# AIRZAI_LED_SENSE_FLEX_REVA.net
KiCad netlist of a schematic drawn in Altium Designer
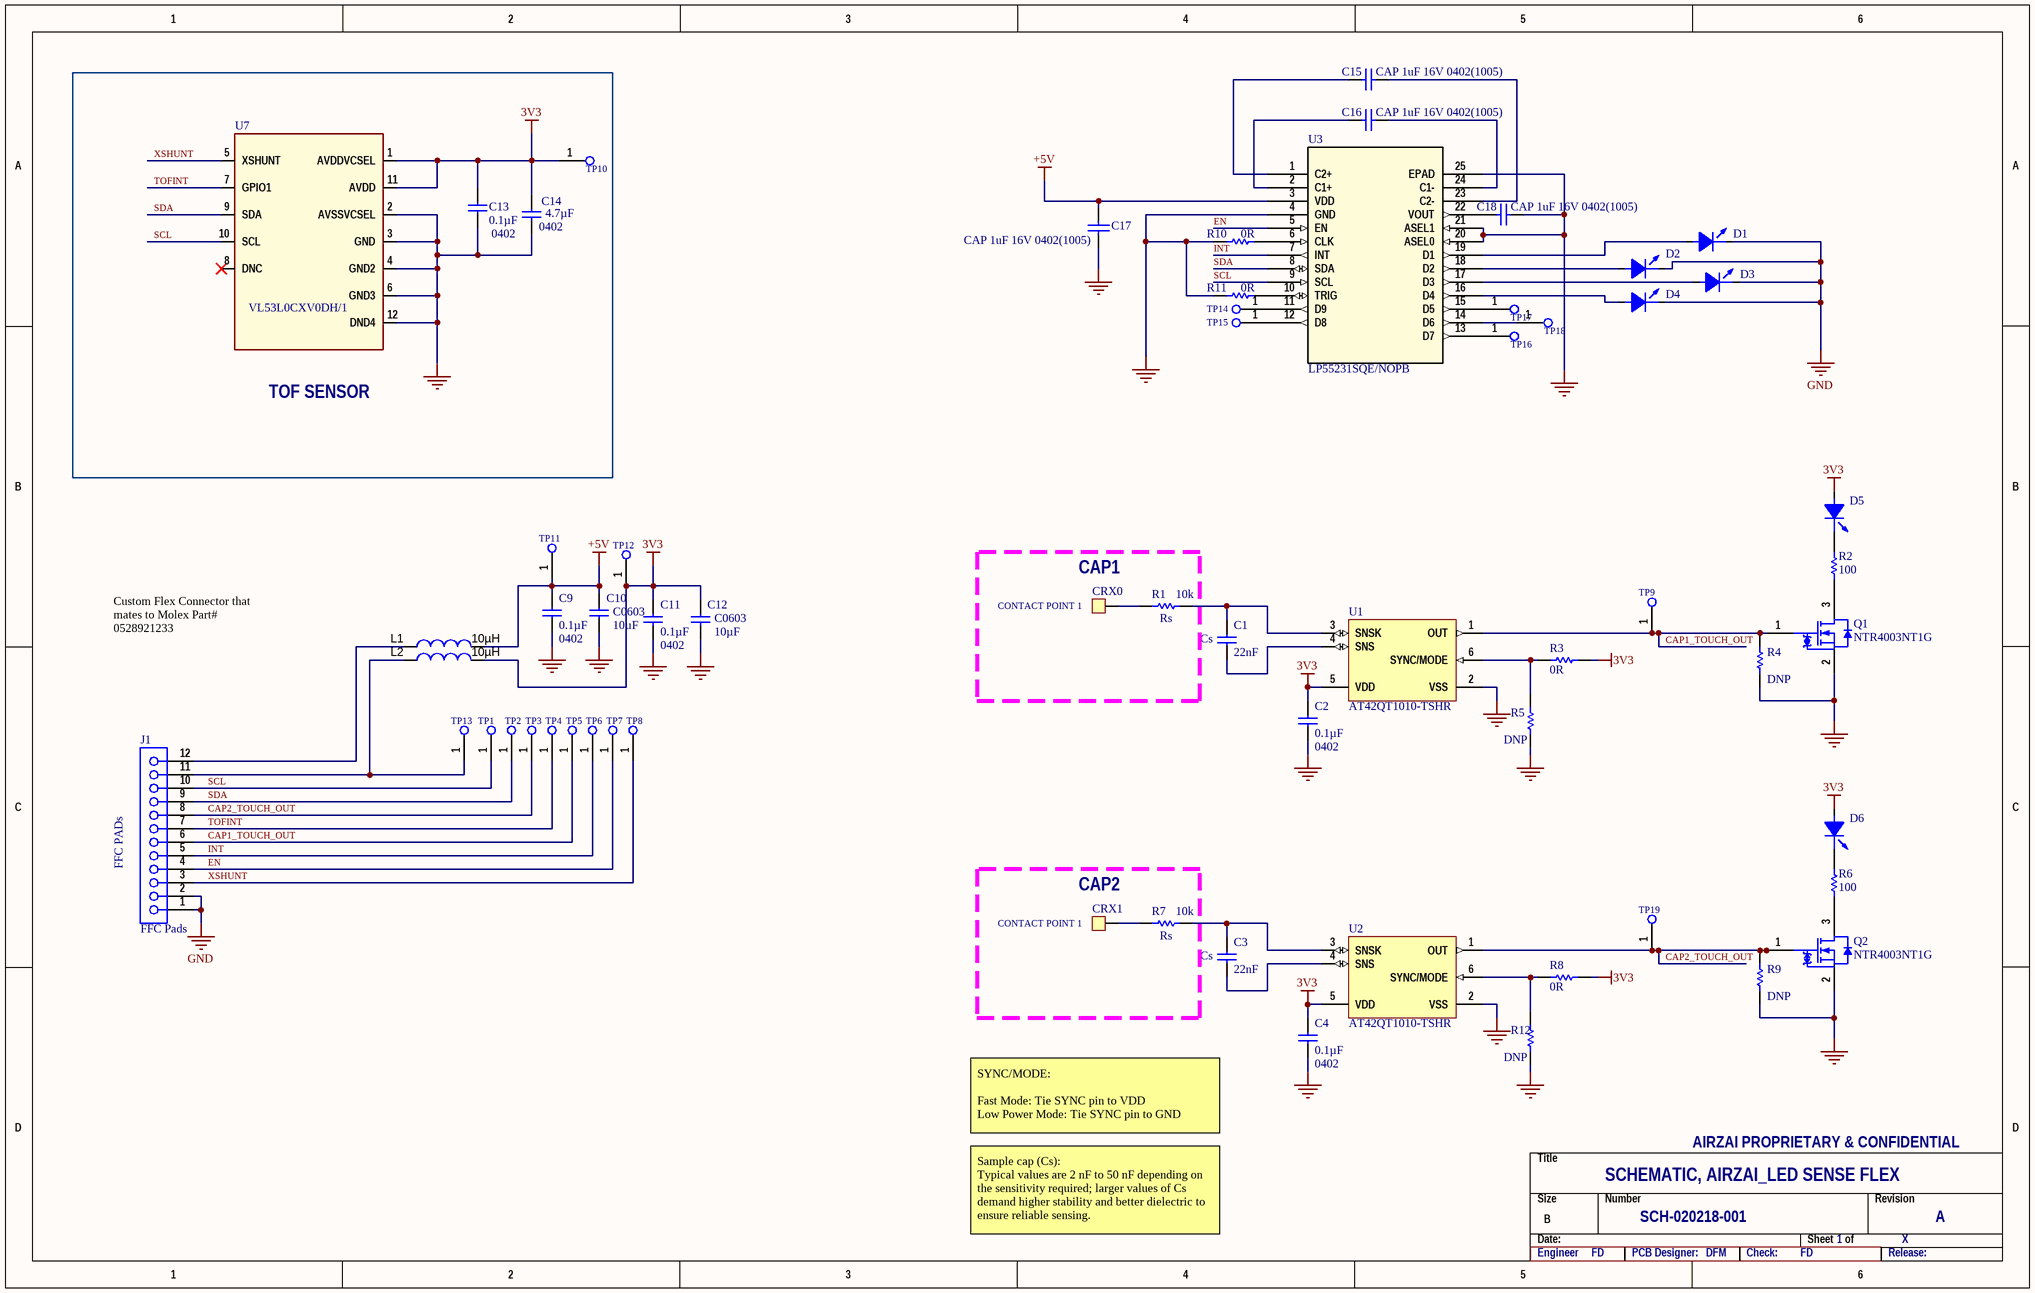
[diagram p0: AIRZAI_LED_SENSE_FLEX_REVA.SchDoc]

(export (version "E")
  (design (tool "Eeschema 10.0.6"))
  (components
    (comp (ref "C1")
      (value "22nF")
      (footprint "0402CAP")
      (description "Capacitor, X7R, ±10%")
      (fields
        (field (name "MANUFACTURER") "TDK")
        (field (name "MANUFACTURER PART NUMBER") "CGA2B2X7R1E223K050BA")
      )
      (libsource (lib "Nordic Passive DB") (part "CAP"))
    )
    (comp (ref "C2")
      (value "0.1µF")
      (footprint "0402")
      (description "Capacitor, X7R, ±10%")
      (fields (field (name "MANUFACTURER") "TDK") (field (name "MANUFACTURER PART NUMBER") "C1005X7R1C104K"))
      (libsource (lib "Nordic Passive DB") (part "CAP"))
    )
    (comp (ref "C3")
      (value "22nF")
      (footprint "0402CAP")
      (description "Capacitor, X7R, ±10%")
      (fields
        (field (name "MANUFACTURER") "TDK")
        (field (name "MANUFACTURER PART NUMBER") "CGA2B2X7R1E223K050BA")
      )
      (libsource (lib "Nordic Passive DB") (part "CAP"))
    )
    (comp (ref "C4")
      (value "0.1µF")
      (footprint "0402")
      (description "Capacitor, X7R, ±10%")
      (fields (field (name "MANUFACTURER") "TDK") (field (name "MANUFACTURER PART NUMBER") "C1005X7R1C104K"))
      (libsource (lib "Nordic Passive DB") (part "CAP"))
    )
    (comp (ref "C9")
      (value "0.1µF")
      (footprint "0402")
      (description "Capacitor, X7R, ±10%")
      (fields (field (name "MANUFACTURER") "TDK") (field (name "MANUFACTURER PART NUMBER") "C1005X7R1C104K"))
      (libsource (lib "Nordic Passive DB") (part "CAP"))
    )
    (comp (ref "C10")
      (value "10µF")
      (footprint "C0603")
      (description "Capacitor, X7R, ±10%")
      (fields
        (field (name "MANUFACTURER") "MURATA")
        (field (name "MANUFACTURER PART NUMBER") "GRM188R60J106ME47D")
      )
      (libsource (lib "Nordic Passive DB") (part "CAP"))
    )
    (comp (ref "C11")
      (value "0.1µF")
      (footprint "0402")
      (description "Capacitor, X7R, ±10%")
      (fields (field (name "MANUFACTURER") "TDK") (field (name "MANUFACTURER PART NUMBER") "C1005X7R1C104K"))
      (libsource (lib "Nordic Passive DB") (part "CAP"))
    )
    (comp (ref "C12")
      (value "10µF")
      (footprint "C0603")
      (description "Capacitor, X7R, ±10%")
      (fields
        (field (name "MANUFACTURER") "MURATA")
        (field (name "MANUFACTURER PART NUMBER") "GRM188R60J106ME47D")
      )
      (libsource (lib "Nordic Passive DB") (part "CAP"))
    )
    (comp (ref "C13")
      (value "0.1µF")
      (footprint "0402")
      (description "Capacitor, X7R, ±10%")
      (fields (field (name "MANUFACTURER") "TDK") (field (name "MANUFACTURER PART NUMBER") "C1005X7R1C104K"))
      (libsource (lib "Nordic Passive DB") (part "CAP"))
    )
    (comp (ref "C14")
      (value "4.7µF")
      (footprint "0402")
      (description "Capacitor, X7R, ±10%")
      (fields (field (name "MANUFACTURER") "TDK") (field (name "MANUFACTURER PART NUMBER") "C1005X5R0J475M"))
      (libsource (lib "Nordic Passive DB") (part "CAP"))
    )
    (comp (ref "C15")
      (value "CAP 1uF 16V 0402(1005)")
      (footprint "CAPC0402(1005)60_M")
      (description "CAP 1uF 16V ±10% 0402 (1005 Metric) Thickness 0.6mm SMD")
      (fields (field (name "TOLERANCE") "Â±10%") (field (name "MANUFACTURER") "Taiyo Yuden"))
      (libsource (lib "AIRZAI_LED_SENSE_FLEX_REVA") (part "CAP"))
    )
    (comp (ref "C16")
      (value "CAP 1uF 16V 0402(1005)")
      (footprint "CAPC0402(1005)60_M")
      (description "CAP 1uF 16V ±10% 0402 (1005 Metric) Thickness 0.6mm SMD")
      (fields (field (name "TOLERANCE") "Â±10%") (field (name "MANUFACTURER") "Taiyo Yuden"))
      (libsource (lib "AIRZAI_LED_SENSE_FLEX_REVA") (part "CAP"))
    )
    (comp (ref "C17")
      (value "CAP 1uF 16V 0402(1005)")
      (footprint "CAPC0402(1005)60_M")
      (description "CAP 1uF 16V ±10% 0402 (1005 Metric) Thickness 0.6mm SMD")
      (fields (field (name "TOLERANCE") "Â±10%") (field (name "MANUFACTURER") "Taiyo Yuden"))
      (libsource (lib "AIRZAI_LED_SENSE_FLEX_REVA") (part "CAP"))
    )
    (comp (ref "C18")
      (value "CAP 1uF 16V 0402(1005)")
      (footprint "CAPC0402(1005)60_M")
      (description "CAP 1uF 16V ±10% 0402 (1005 Metric) Thickness 0.6mm SMD")
      (fields (field (name "TOLERANCE") "Â±10%") (field (name "MANUFACTURER") "Taiyo Yuden"))
      (libsource (lib "AIRZAI_LED_SENSE_FLEX_REVA") (part "CAP"))
    )
    (comp (ref "CRX0")
      (value "CONTACT POINT 1")
      (footprint "CONTACT_POINT_1CM _SQ")
      (libsource (lib "AIRZAI_LED_SENSE_FLEX_REVA") (part "WIRE_POINT"))
    )
    (comp (ref "CRX1")
      (value "CONTACT POINT 1")
      (footprint "CONTACT_POINT_1CM _SQ")
      (libsource (lib "AIRZAI_LED_SENSE_FLEX_REVA") (part "WIRE_POINT"))
    )
    (comp (ref "D1")
      (value "WHITE")
      (footprint "LED1206_LTW-C230DS")
      (fields (field (name "MANUFACTURER PART NUMBER") "LTW-C230DS") (field (name "MANUFACTURER") "LITEON"))
      (libsource (lib "AIRZAI_LED_SENSE_FLEX_REVA") (part "LED_LTW-C230DS"))
    )
    (comp (ref "D2")
      (value "WHITE")
      (footprint "LED1206_LTW-C230DS")
      (fields (field (name "MANUFACTURER PART NUMBER") "LTW-C230DS") (field (name "MANUFACTURER") "LITEON"))
      (libsource (lib "AIRZAI_LED_SENSE_FLEX_REVA") (part "LED_LTW-C230DS"))
    )
    (comp (ref "D3")
      (value "WHITE")
      (footprint "LED1206_LTW-C230DS")
      (fields (field (name "MANUFACTURER PART NUMBER") "LTW-C230DS") (field (name "MANUFACTURER") "LITEON"))
      (libsource (lib "AIRZAI_LED_SENSE_FLEX_REVA") (part "LED_LTW-C230DS"))
    )
    (comp (ref "D4")
      (value "WHITE")
      (footprint "LED1206_LTW-C230DS")
      (fields (field (name "MANUFACTURER PART NUMBER") "LTW-C230DS") (field (name "MANUFACTURER") "LITEON"))
      (libsource (lib "AIRZAI_LED_SENSE_FLEX_REVA") (part "LED_LTW-C230DS"))
    )
    (comp (ref "D5")
      (value "WHITE")
      (footprint "LED1206_LTW-C230DS")
      (fields (field (name "MANUFACTURER PART NUMBER") "LTW-C230DS") (field (name "MANUFACTURER") "LITEON"))
      (libsource (lib "AIRZAI_LED_SENSE_FLEX_REVA") (part "LED_LTW-C230DS"))
    )
    (comp (ref "D6")
      (value "WHITE")
      (footprint "LED1206_LTW-C230DS")
      (fields (field (name "MANUFACTURER PART NUMBER") "LTW-C230DS") (field (name "MANUFACTURER") "LITEON"))
      (libsource (lib "AIRZAI_LED_SENSE_FLEX_REVA") (part "LED_LTW-C230DS"))
    )
    (comp (ref "J1")
      (value "FFC Pads")
      (footprint "FFC_Pads")
      (description "0.5 mm Pitch FFC Pads")
      (libsource (lib "AIRZAI_LED_SENSE_FLEX_REVA") (part "FFC_PADS"))
    )
    (comp (ref "L1")
      (value "CB2012T100KR")
      (footprint "0805")
      (description "Inductor, 10 µH, 0.5A, 0.65 ohm, SMD")
      (fields
        (field (name "MANUFACTURER") "Taiyo Yuden")
        (field (name "TOLERANCE") "10%")
        (field (name "VALUEDISPLAYED") "10µH")
      )
      (libsource (lib "AIRZAI_LED_SENSE_FLEX_REVA") (part "CB2012T100KR"))
    )
    (comp (ref "L2")
      (value "CB2012T100KR")
      (footprint "0805")
      (description "Inductor, 10 µH, 0.5A, 0.65 ohm, SMD")
      (fields
        (field (name "MANUFACTURER") "Taiyo Yuden")
        (field (name "TOLERANCE") "10%")
        (field (name "VALUEDISPLAYED") "10µH")
      )
      (libsource (lib "AIRZAI_LED_SENSE_FLEX_REVA") (part "CB2012T100KR"))
    )
    (comp (ref "Q1")
      (value "NTR4003NT1G")
      (footprint "SOT-23-3-NTR4003NT1G")
      (description "N-Channel 30V 500mA (Ta) 690mW (Ta) Surface Mount SOT-23-3 (TO-236)")
      (fields (field (name "MANUFACTURER") "ON Semiconductor"))
      (libsource (lib "AIRZAI_LED_SENSE_FLEX_REVA") (part "NTR4003NT1G"))
    )
    (comp (ref "Q2")
      (value "NTR4003NT1G")
      (footprint "SOT-23-3-NTR4003NT1G")
      (description "N-Channel 30V 500mA (Ta) 690mW (Ta) Surface Mount SOT-23-3 (TO-236)")
      (fields (field (name "MANUFACTURER") "ON Semiconductor"))
      (libsource (lib "AIRZAI_LED_SENSE_FLEX_REVA") (part "NTR4003NT1G"))
    )
    (comp (ref "R1")
      (value "10k")
      (footprint "0402")
      (description "10k 0.063W 1% 0402 (1005 Metric)  SMD")
      (fields (field (name "TOLERANCE") "None") (field (name "POWER") "0.063W"))
      (libsource (lib "AIRZAI_LED_SENSE_FLEX_REVA") (part "RES"))
    )
    (comp (ref "R2")
      (value "100")
      (footprint "0402")
      (description "100 0.063W 1% 0402 (1005 Metric)  SMD")
      (fields (field (name "TOLERANCE") "None") (field (name "MANUFACTURER") "Yageo"))
      (libsource (lib "AIRZAI_LED_SENSE_FLEX_REVA") (part "RES"))
    )
    (comp (ref "R3")
      (value "0R")
      (footprint "0402")
      (description "Jumper 0402 (1005 Metric)")
      (fields (field (name "TOLERANCE") "None") (field (name "MANUFACTURER") "Panasonic"))
      (libsource (lib "AIRZAI_LED_SENSE_FLEX_REVA") (part "RES"))
    )
    (comp (ref "R4")
      (value "DNP")
      (footprint "0402")
      (fields
        (field (name "TOLERANCE") "None")
        (field (name "POWER") "0.0625 W")
        (field (name "Comment") "DNP 0402(1005)")
      )
      (libsource (lib "AIRZAI_LED_SENSE_FLEX_REVA") (part "RES"))
    )
    (comp (ref "R5")
      (value "DNP")
      (footprint "0402")
      (fields
        (field (name "TOLERANCE") "None")
        (field (name "POWER") "0.0625 W")
        (field (name "Comment") "DNP 0402(1005)")
      )
      (libsource (lib "AIRZAI_LED_SENSE_FLEX_REVA") (part "RES"))
    )
    (comp (ref "R6")
      (value "100")
      (footprint "0402")
      (description "100 0.063W 1% 0402 (1005 Metric)  SMD")
      (fields (field (name "TOLERANCE") "None") (field (name "MANUFACTURER") "Yageo"))
      (libsource (lib "AIRZAI_LED_SENSE_FLEX_REVA") (part "RES"))
    )
    (comp (ref "R7")
      (value "10k")
      (footprint "0402")
      (description "10k 0.063W 1% 0402 (1005 Metric)  SMD")
      (fields (field (name "TOLERANCE") "None") (field (name "POWER") "0.063W"))
      (libsource (lib "AIRZAI_LED_SENSE_FLEX_REVA") (part "RES"))
    )
    (comp (ref "R8")
      (value "0R")
      (footprint "0402")
      (description "Jumper 0402 (1005 Metric)")
      (fields (field (name "TOLERANCE") "None") (field (name "MANUFACTURER") "Panasonic"))
      (libsource (lib "AIRZAI_LED_SENSE_FLEX_REVA") (part "RES"))
    )
    (comp (ref "R9")
      (value "DNP")
      (footprint "0402")
      (fields
        (field (name "TOLERANCE") "None")
        (field (name "POWER") "0.0625 W")
        (field (name "Comment") "DNP 0402(1005)")
      )
      (libsource (lib "AIRZAI_LED_SENSE_FLEX_REVA") (part "RES"))
    )
    (comp (ref "R10")
      (value "0R")
      (footprint "0402")
      (description "Jumper 0402 (1005 Metric)")
      (fields (field (name "TOLERANCE") "None") (field (name "MANUFACTURER") "Panasonic"))
      (libsource (lib "AIRZAI_LED_SENSE_FLEX_REVA") (part "RES"))
    )
    (comp (ref "R11")
      (value "0R")
      (footprint "0402")
      (description "Jumper 0402 (1005 Metric)")
      (fields (field (name "TOLERANCE") "None") (field (name "MANUFACTURER") "Panasonic"))
      (libsource (lib "AIRZAI_LED_SENSE_FLEX_REVA") (part "RES"))
    )
    (comp (ref "R12")
      (value "DNP")
      (footprint "0402")
      (fields
        (field (name "TOLERANCE") "None")
        (field (name "POWER") "0.0625 W")
        (field (name "Comment") "DNP 0402(1005)")
      )
      (libsource (lib "AIRZAI_LED_SENSE_FLEX_REVA") (part "RES"))
    )
    (comp (ref "TP1")
      (value "Test Point")
      (footprint "TP_0.9MM")
      (libsource (lib "AIRZAI_LED_SENSE_FLEX_REVA") (part "Test Point"))
    )
    (comp (ref "TP2")
      (value "Test Point")
      (footprint "TP_0.9MM")
      (libsource (lib "AIRZAI_LED_SENSE_FLEX_REVA") (part "Test Point"))
    )
    (comp (ref "TP3")
      (value "Test Point")
      (footprint "TP_0.9MM")
      (libsource (lib "AIRZAI_LED_SENSE_FLEX_REVA") (part "Test Point"))
    )
    (comp (ref "TP4")
      (value "Test Point")
      (footprint "TP_0.9MM")
      (libsource (lib "AIRZAI_LED_SENSE_FLEX_REVA") (part "Test Point"))
    )
    (comp (ref "TP5")
      (value "Test Point")
      (footprint "TP_0.9MM")
      (libsource (lib "AIRZAI_LED_SENSE_FLEX_REVA") (part "Test Point"))
    )
    (comp (ref "TP6")
      (value "Test Point")
      (footprint "TP_0.9MM")
      (libsource (lib "AIRZAI_LED_SENSE_FLEX_REVA") (part "Test Point"))
    )
    (comp (ref "TP7")
      (value "Test Point")
      (footprint "TP_0.9MM")
      (libsource (lib "AIRZAI_LED_SENSE_FLEX_REVA") (part "Test Point"))
    )
    (comp (ref "TP8")
      (value "Test Point")
      (footprint "TP_0.9MM")
      (libsource (lib "AIRZAI_LED_SENSE_FLEX_REVA") (part "Test Point"))
    )
    (comp (ref "TP9")
      (value "Test Point")
      (footprint "TP_0.9MM")
      (libsource (lib "AIRZAI_LED_SENSE_FLEX_REVA") (part "Test Point"))
    )
    (comp (ref "TP10")
      (value "Test Point")
      (footprint "TP_0.9MM")
      (libsource (lib "AIRZAI_LED_SENSE_FLEX_REVA") (part "Test Point"))
    )
    (comp (ref "TP11")
      (value "Test Point")
      (footprint "TP_0.9MM")
      (libsource (lib "AIRZAI_LED_SENSE_FLEX_REVA") (part "Test Point"))
    )
    (comp (ref "TP12")
      (value "Test Point")
      (footprint "TP_0.9MM")
      (libsource (lib "AIRZAI_LED_SENSE_FLEX_REVA") (part "Test Point"))
    )
    (comp (ref "TP13")
      (value "Test Point")
      (footprint "TP_0.9MM")
      (libsource (lib "AIRZAI_LED_SENSE_FLEX_REVA") (part "Test Point"))
    )
    (comp (ref "TP14")
      (value "Test Point")
      (footprint "TP_0.9MM")
      (libsource (lib "AIRZAI_LED_SENSE_FLEX_REVA") (part "Test Point"))
    )
    (comp (ref "TP15")
      (value "Test Point")
      (footprint "TP_0.9MM")
      (libsource (lib "AIRZAI_LED_SENSE_FLEX_REVA") (part "Test Point"))
    )
    (comp (ref "TP16")
      (value "Test Point")
      (footprint "TP_0.9MM")
      (libsource (lib "AIRZAI_LED_SENSE_FLEX_REVA") (part "Test Point"))
    )
    (comp (ref "TP17")
      (value "Test Point")
      (footprint "TP_0.9MM")
      (libsource (lib "AIRZAI_LED_SENSE_FLEX_REVA") (part "Test Point"))
    )
    (comp (ref "TP18")
      (value "Test Point")
      (footprint "TP_0.9MM")
      (libsource (lib "AIRZAI_LED_SENSE_FLEX_REVA") (part "Test Point"))
    )
    (comp (ref "TP19")
      (value "Test Point")
      (footprint "TP_0.9MM")
      (libsource (lib "AIRZAI_LED_SENSE_FLEX_REVA") (part "Test Point"))
    )
    (comp (ref "U1")
      (value "AT42QT1010-TSHR")
      (footprint "SOT-23-6-AT42QT1010-TSHR")
      (description "One-channel Touch Sensor IC with Reset Timer, -40° to +85° C, 6-pin SOT23")
      (libsource (lib "AIRZAI_LED_SENSE_FLEX_REVA") (part "AT42QT1010-TSHR"))
    )
    (comp (ref "U2")
      (value "AT42QT1010-TSHR")
      (footprint "SOT-23-6-AT42QT1010-TSHR")
      (description "One-channel Touch Sensor IC with Reset Timer, -40° to +85° C, 6-pin SOT23")
      (libsource (lib "AIRZAI_LED_SENSE_FLEX_REVA") (part "AT42QT1010-TSHR"))
    )
    (comp (ref "U3")
      (value "LP55231SQE/NOPB")
      (footprint "WQFN-24-LP55231SQE/NOPB")
      (description "Imported")
      (fields (field (name "MANUFACTURER") "TI") (field (name "TOLERANCE") "None"))
      (libsource (lib "AltiumDesigner") (part "LP55231SQE/NOPB"))
    )
    (comp (ref "U7")
      (value "VL53L0CXV0DH/1")
      (footprint "VL53L0X")
      (fields (field (name "MANUFACTURER") "ST") (field (name "TOLERANCE") "None"))
      (libsource (lib "DFM_JBKEGSVS_Library") (part "VL53L0X"))
    )
  )
  (nets
    (net (code "1") (name "+5V") (class "Default")
      (node (ref "C10") (pin "1") (pinfunction "1_1") (pintype "passive"))
      (node (ref "C17") (pin "2") (pinfunction "2_2") (pintype "passive"))
      (node (ref "C9") (pin "1") (pinfunction "1_1") (pintype "passive"))
      (node (ref "L1") (pin "2") (pinfunction "2_2") (pintype "passive"))
      (node (ref "TP11") (pin "1") (pinfunction "1_1") (pintype "passive"))
      (node (ref "U3") (pin "3") (pinfunction "VDD_3") (pintype "power_in"))
    )
    (net (code "2") (name "/CAP1_TOUCH_OUT") (class "Default")
      (node (ref "J1") (pin "6") (pinfunction "6_6") (pintype "passive"))
      (node (ref "Q1") (pin "1") (pinfunction "G_1") (pintype "passive"))
      (node (ref "R4") (pin "1") (pinfunction "1_1") (pintype "passive"))
      (node (ref "TP5") (pin "1") (pinfunction "1_1") (pintype "passive"))
      (node (ref "TP9") (pin "1") (pinfunction "1_1") (pintype "passive"))
      (node (ref "U1") (pin "1") (pinfunction "OUT_1") (pintype "output"))
    )
    (net (code "3") (name "/CAP2_TOUCH_OUT") (class "Default")
      (node (ref "J1") (pin "8") (pinfunction "8_8") (pintype "passive"))
      (node (ref "Q2") (pin "1") (pinfunction "G_1") (pintype "passive"))
      (node (ref "R9") (pin "1") (pinfunction "1_1") (pintype "passive"))
      (node (ref "TP19") (pin "1") (pinfunction "1_1") (pintype "passive"))
      (node (ref "TP3") (pin "1") (pinfunction "1_1") (pintype "passive"))
      (node (ref "U2") (pin "1") (pinfunction "OUT_1") (pintype "output"))
    )
    (net (code "4") (name "/EN") (class "Default")
      (node (ref "J1") (pin "4") (pinfunction "4_4") (pintype "passive"))
      (node (ref "TP7") (pin "1") (pinfunction "1_1") (pintype "passive"))
      (node (ref "U3") (pin "5") (pinfunction "EN_5") (pintype "input"))
    )
    (net (code "5") (name "/INT") (class "Default")
      (node (ref "J1") (pin "5") (pinfunction "5_5") (pintype "passive"))
      (node (ref "TP6") (pin "1") (pinfunction "1_1") (pintype "passive"))
      (node (ref "U3") (pin "7") (pinfunction "INT_7") (pintype "output"))
    )
    (net (code "6") (name "/SCL") (class "Default")
      (node (ref "J1") (pin "10") (pinfunction "10_10") (pintype "passive"))
      (node (ref "TP1") (pin "1") (pinfunction "1_1") (pintype "passive"))
      (node (ref "U3") (pin "9") (pinfunction "SCL_9") (pintype "input"))
      (node (ref "U7") (pin "10") (pinfunction "SCL_10") (pintype "passive"))
    )
    (net (code "7") (name "/SDA") (class "Default")
      (node (ref "J1") (pin "9") (pinfunction "9_9") (pintype "passive"))
      (node (ref "TP2") (pin "1") (pinfunction "1_1") (pintype "passive"))
      (node (ref "U3") (pin "8") (pinfunction "SDA_8") (pintype "bidirectional"))
      (node (ref "U7") (pin "9") (pinfunction "SDA_9") (pintype "passive"))
    )
    (net (code "8") (name "/TOFINT") (class "Default")
      (node (ref "J1") (pin "7") (pinfunction "7_7") (pintype "passive"))
      (node (ref "TP4") (pin "1") (pinfunction "1_1") (pintype "passive"))
      (node (ref "U7") (pin "7") (pinfunction "GPIO1_7") (pintype "passive"))
    )
    (net (code "9") (name "/XSHUNT") (class "Default")
      (node (ref "J1") (pin "3") (pinfunction "3_3") (pintype "passive"))
      (node (ref "TP8") (pin "1") (pinfunction "1_1") (pintype "passive"))
      (node (ref "U7") (pin "5") (pinfunction "XSHUNT_5") (pintype "passive"))
    )
    (net (code "10") (name "3V3") (class "Default")
      (node (ref "C11") (pin "1") (pinfunction "1_1") (pintype "passive"))
      (node (ref "C12") (pin "1") (pinfunction "1_1") (pintype "passive"))
      (node (ref "C13") (pin "1") (pinfunction "1_1") (pintype "passive"))
      (node (ref "C14") (pin "2") (pinfunction "2_2") (pintype "passive"))
      (node (ref "C2") (pin "1") (pinfunction "1_1") (pintype "passive"))
      (node (ref "C4") (pin "1") (pinfunction "1_1") (pintype "passive"))
      (node (ref "D5") (pin "2") (pinfunction "ANODE_2") (pintype "passive"))
      (node (ref "D6") (pin "2") (pinfunction "ANODE_2") (pintype "passive"))
      (node (ref "L2") (pin "2") (pinfunction "2_2") (pintype "passive"))
      (node (ref "R3") (pin "2") (pinfunction "2_2") (pintype "passive"))
      (node (ref "R8") (pin "2") (pinfunction "2_2") (pintype "passive"))
      (node (ref "TP10") (pin "1") (pinfunction "1_1") (pintype "passive"))
      (node (ref "TP12") (pin "1") (pinfunction "1_1") (pintype "passive"))
      (node (ref "U1") (pin "5") (pinfunction "VDD_5") (pintype "power_in"))
      (node (ref "U2") (pin "5") (pinfunction "VDD_5") (pintype "power_in"))
      (node (ref "U7") (pin "1") (pinfunction "AVDDVCSEL_1") (pintype "passive"))
      (node (ref "U7") (pin "11") (pinfunction "AVDD_11") (pintype "passive"))
    )
    (net (code "11") (name "GND") (class "Default")
      (node (ref "C10") (pin "2") (pinfunction "2_2") (pintype "passive"))
      (node (ref "C11") (pin "2") (pinfunction "2_2") (pintype "passive"))
      (node (ref "C12") (pin "2") (pinfunction "2_2") (pintype "passive"))
      (node (ref "C13") (pin "2") (pinfunction "2_2") (pintype "passive"))
      (node (ref "C14") (pin "1") (pinfunction "1_1") (pintype "passive"))
      (node (ref "C17") (pin "1") (pinfunction "1_1") (pintype "passive"))
      (node (ref "C18") (pin "2") (pinfunction "2_2") (pintype "passive"))
      (node (ref "C2") (pin "2") (pinfunction "2_2") (pintype "passive"))
      (node (ref "C4") (pin "2") (pinfunction "2_2") (pintype "passive"))
      (node (ref "C9") (pin "2") (pinfunction "2_2") (pintype "passive"))
      (node (ref "D1") (pin "1") (pinfunction "CATHODE_1") (pintype "passive"))
      (node (ref "D2") (pin "1") (pinfunction "CATHODE_1") (pintype "passive"))
      (node (ref "D3") (pin "1") (pinfunction "CATHODE_1") (pintype "passive"))
      (node (ref "D4") (pin "1") (pinfunction "CATHODE_1") (pintype "passive"))
      (node (ref "J1") (pin "1") (pinfunction "1_1") (pintype "passive"))
      (node (ref "J1") (pin "2") (pinfunction "2_2") (pintype "passive"))
      (node (ref "Q1") (pin "2") (pinfunction "S_2") (pintype "passive"))
      (node (ref "Q2") (pin "2") (pinfunction "S_2") (pintype "passive"))
      (node (ref "R10") (pin "1") (pinfunction "1_1") (pintype "passive"))
      (node (ref "R11") (pin "1") (pinfunction "1_1") (pintype "passive"))
      (node (ref "R12") (pin "2") (pinfunction "2_2") (pintype "passive"))
      (node (ref "R4") (pin "2") (pinfunction "2_2") (pintype "passive"))
      (node (ref "R5") (pin "2") (pinfunction "2_2") (pintype "passive"))
      (node (ref "R9") (pin "2") (pinfunction "2_2") (pintype "passive"))
      (node (ref "U1") (pin "2") (pinfunction "VSS_2") (pintype "power_in"))
      (node (ref "U2") (pin "2") (pinfunction "VSS_2") (pintype "power_in"))
      (node (ref "U3") (pin "20") (pinfunction "ASEL0_20") (pintype "input"))
      (node (ref "U3") (pin "21") (pinfunction "ASEL1_21") (pintype "input"))
      (node (ref "U3") (pin "25") (pinfunction "EPAD_25") (pintype "passive"))
      (node (ref "U3") (pin "4") (pinfunction "GND_4") (pintype "power_in"))
      (node (ref "U7") (pin "12") (pinfunction "DND4_12") (pintype "passive"))
      (node (ref "U7") (pin "2") (pinfunction "AVSSVCSEL_2") (pintype "passive"))
      (node (ref "U7") (pin "3") (pinfunction "GND_3") (pintype "passive"))
      (node (ref "U7") (pin "4") (pinfunction "GND2_4") (pintype "passive"))
      (node (ref "U7") (pin "6") (pinfunction "GND3_6") (pintype "passive"))
    )
    (net (code "12") (name "Net-(CRX0-Pad1)") (class "Default")
      (node (ref "CRX0") (pin "1") (pinfunction "1_1") (pintype "passive"))
      (node (ref "R1") (pin "2") (pinfunction "2_2") (pintype "passive"))
    )
    (net (code "13") (name "Net-(CRX1-Pad1)") (class "Default")
      (node (ref "CRX1") (pin "1") (pinfunction "1_1") (pintype "passive"))
      (node (ref "R7") (pin "2") (pinfunction "2_2") (pintype "passive"))
    )
    (net (code "14") (name "Net-(D1-ANODE)") (class "Default")
      (node (ref "D1") (pin "2") (pinfunction "ANODE_2") (pintype "passive"))
      (node (ref "U3") (pin "19") (pinfunction "D1_19") (pintype "output"))
    )
    (net (code "15") (name "Net-(D2-ANODE)") (class "Default")
      (node (ref "D2") (pin "2") (pinfunction "ANODE_2") (pintype "passive"))
      (node (ref "U3") (pin "18") (pinfunction "D2_18") (pintype "output"))
    )
    (net (code "16") (name "Net-(D3-ANODE)") (class "Default")
      (node (ref "D3") (pin "2") (pinfunction "ANODE_2") (pintype "passive"))
      (node (ref "U3") (pin "17") (pinfunction "D3_17") (pintype "output"))
    )
    (net (code "17") (name "Net-(D4-ANODE)") (class "Default")
      (node (ref "D4") (pin "2") (pinfunction "ANODE_2") (pintype "passive"))
      (node (ref "U3") (pin "16") (pinfunction "D4_16") (pintype "output"))
    )
    (net (code "18") (name "Net-(D5-CATHODE)") (class "Default")
      (node (ref "D5") (pin "1") (pinfunction "CATHODE_1") (pintype "passive"))
      (node (ref "R2") (pin "2") (pinfunction "2_2") (pintype "passive"))
    )
    (net (code "19") (name "Net-(D6-CATHODE)") (class "Default")
      (node (ref "D6") (pin "1") (pinfunction "CATHODE_1") (pintype "passive"))
      (node (ref "R6") (pin "2") (pinfunction "2_2") (pintype "passive"))
    )
    (net (code "20") (name "Net-(J1-Pad11)") (class "Default")
      (node (ref "J1") (pin "11") (pinfunction "11_11") (pintype "passive"))
      (node (ref "L2") (pin "1") (pinfunction "1_1") (pintype "passive"))
      (node (ref "TP13") (pin "1") (pinfunction "1_1") (pintype "passive"))
    )
    (net (code "21") (name "Net-(J1-Pad12)") (class "Default")
      (node (ref "J1") (pin "12") (pinfunction "12_12") (pintype "passive"))
      (node (ref "L1") (pin "1") (pinfunction "1_1") (pintype "passive"))
    )
    (net (code "22") (name "Net-(Q1-D)") (class "Default")
      (node (ref "Q1") (pin "3") (pinfunction "D_3") (pintype "passive"))
      (node (ref "R2") (pin "1") (pinfunction "1_1") (pintype "passive"))
    )
    (net (code "23") (name "Net-(Q2-D)") (class "Default")
      (node (ref "Q2") (pin "3") (pinfunction "D_3") (pintype "passive"))
      (node (ref "R6") (pin "1") (pinfunction "1_1") (pintype "passive"))
    )
    (net (code "24") (name "Net-(U1-SNS)") (class "Default")
      (node (ref "C1") (pin "2") (pinfunction "2_2") (pintype "passive"))
      (node (ref "U1") (pin "4") (pinfunction "SNS_4") (pintype "bidirectional"))
    )
    (net (code "25") (name "Net-(U1-SNSK)") (class "Default")
      (node (ref "C1") (pin "1") (pinfunction "1_1") (pintype "passive"))
      (node (ref "R1") (pin "1") (pinfunction "1_1") (pintype "passive"))
      (node (ref "U1") (pin "3") (pinfunction "SNSK_3") (pintype "bidirectional"))
    )
    (net (code "26") (name "Net-(U1-SYNC{slash}MODE)") (class "Default")
      (node (ref "R3") (pin "1") (pinfunction "1_1") (pintype "passive"))
      (node (ref "R5") (pin "1") (pinfunction "1_1") (pintype "passive"))
      (node (ref "U1") (pin "6") (pinfunction "SYNC/MODE_6") (pintype "input"))
    )
    (net (code "27") (name "Net-(U2-SNS)") (class "Default")
      (node (ref "C3") (pin "2") (pinfunction "2_2") (pintype "passive"))
      (node (ref "U2") (pin "4") (pinfunction "SNS_4") (pintype "bidirectional"))
    )
    (net (code "28") (name "Net-(U2-SNSK)") (class "Default")
      (node (ref "C3") (pin "1") (pinfunction "1_1") (pintype "passive"))
      (node (ref "R7") (pin "1") (pinfunction "1_1") (pintype "passive"))
      (node (ref "U2") (pin "3") (pinfunction "SNSK_3") (pintype "bidirectional"))
    )
    (net (code "29") (name "Net-(U2-SYNC{slash}MODE)") (class "Default")
      (node (ref "R12") (pin "1") (pinfunction "1_1") (pintype "passive"))
      (node (ref "R8") (pin "1") (pinfunction "1_1") (pintype "passive"))
      (node (ref "U2") (pin "6") (pinfunction "SYNC/MODE_6") (pintype "input"))
    )
    (net (code "30") (name "Net-(U3-C1+)") (class "Default")
      (node (ref "C16") (pin "1") (pinfunction "1_1") (pintype "passive"))
      (node (ref "U3") (pin "2") (pinfunction "C1+_2") (pintype "passive"))
    )
    (net (code "31") (name "Net-(U3-C1-)") (class "Default")
      (node (ref "C16") (pin "2") (pinfunction "2_2") (pintype "passive"))
      (node (ref "U3") (pin "24") (pinfunction "C1-_24") (pintype "passive"))
    )
    (net (code "32") (name "Net-(U3-C2+)") (class "Default")
      (node (ref "C15") (pin "1") (pinfunction "1_1") (pintype "passive"))
      (node (ref "U3") (pin "1") (pinfunction "C2+_1") (pintype "passive"))
    )
    (net (code "33") (name "Net-(U3-C2-)") (class "Default")
      (node (ref "C15") (pin "2") (pinfunction "2_2") (pintype "passive"))
      (node (ref "U3") (pin "23") (pinfunction "C2-_23") (pintype "passive"))
    )
    (net (code "34") (name "Net-(U3-CLK)") (class "Default")
      (node (ref "R10") (pin "2") (pinfunction "2_2") (pintype "passive"))
      (node (ref "U3") (pin "6") (pinfunction "CLK_6") (pintype "input"))
    )
    (net (code "35") (name "Net-(U3-D5)") (class "Default")
      (node (ref "TP17") (pin "1") (pinfunction "1_1") (pintype "passive"))
      (node (ref "U3") (pin "15") (pinfunction "D5_15") (pintype "output"))
    )
    (net (code "36") (name "Net-(U3-D6)") (class "Default")
      (node (ref "TP18") (pin "1") (pinfunction "1_1") (pintype "passive"))
      (node (ref "U3") (pin "14") (pinfunction "D6_14") (pintype "output"))
    )
    (net (code "37") (name "Net-(U3-D7)") (class "Default")
      (node (ref "TP16") (pin "1") (pinfunction "1_1") (pintype "passive"))
      (node (ref "U3") (pin "13") (pinfunction "D7_13") (pintype "output"))
    )
    (net (code "38") (name "Net-(U3-D8)") (class "Default")
      (node (ref "TP15") (pin "1") (pinfunction "1_1") (pintype "passive"))
      (node (ref "U3") (pin "12") (pinfunction "D8_12") (pintype "output"))
    )
    (net (code "39") (name "Net-(U3-D9)") (class "Default")
      (node (ref "TP14") (pin "1") (pinfunction "1_1") (pintype "passive"))
      (node (ref "U3") (pin "11") (pinfunction "D9_11") (pintype "output"))
    )
    (net (code "40") (name "Net-(U3-TRIG)") (class "Default")
      (node (ref "R11") (pin "2") (pinfunction "2_2") (pintype "passive"))
      (node (ref "U3") (pin "10") (pinfunction "TRIG_10") (pintype "bidirectional"))
    )
    (net (code "41") (name "Net-(U3-VOUT)") (class "Default")
      (node (ref "C18") (pin "1") (pinfunction "1_1") (pintype "passive"))
      (node (ref "U3") (pin "22") (pinfunction "VOUT_22") (pintype "output"))
    )
    (net (code "42") (name "unconnected-(U7-DNC-Pad8)") (class "Default")
      (node (ref "U7") (pin "8") (pinfunction "DNC_8") (pintype "passive+no_connect"))
    )
  )
)
